# NRF24L01.net
KiCad netlist of a schematic drawn in Altium Designer
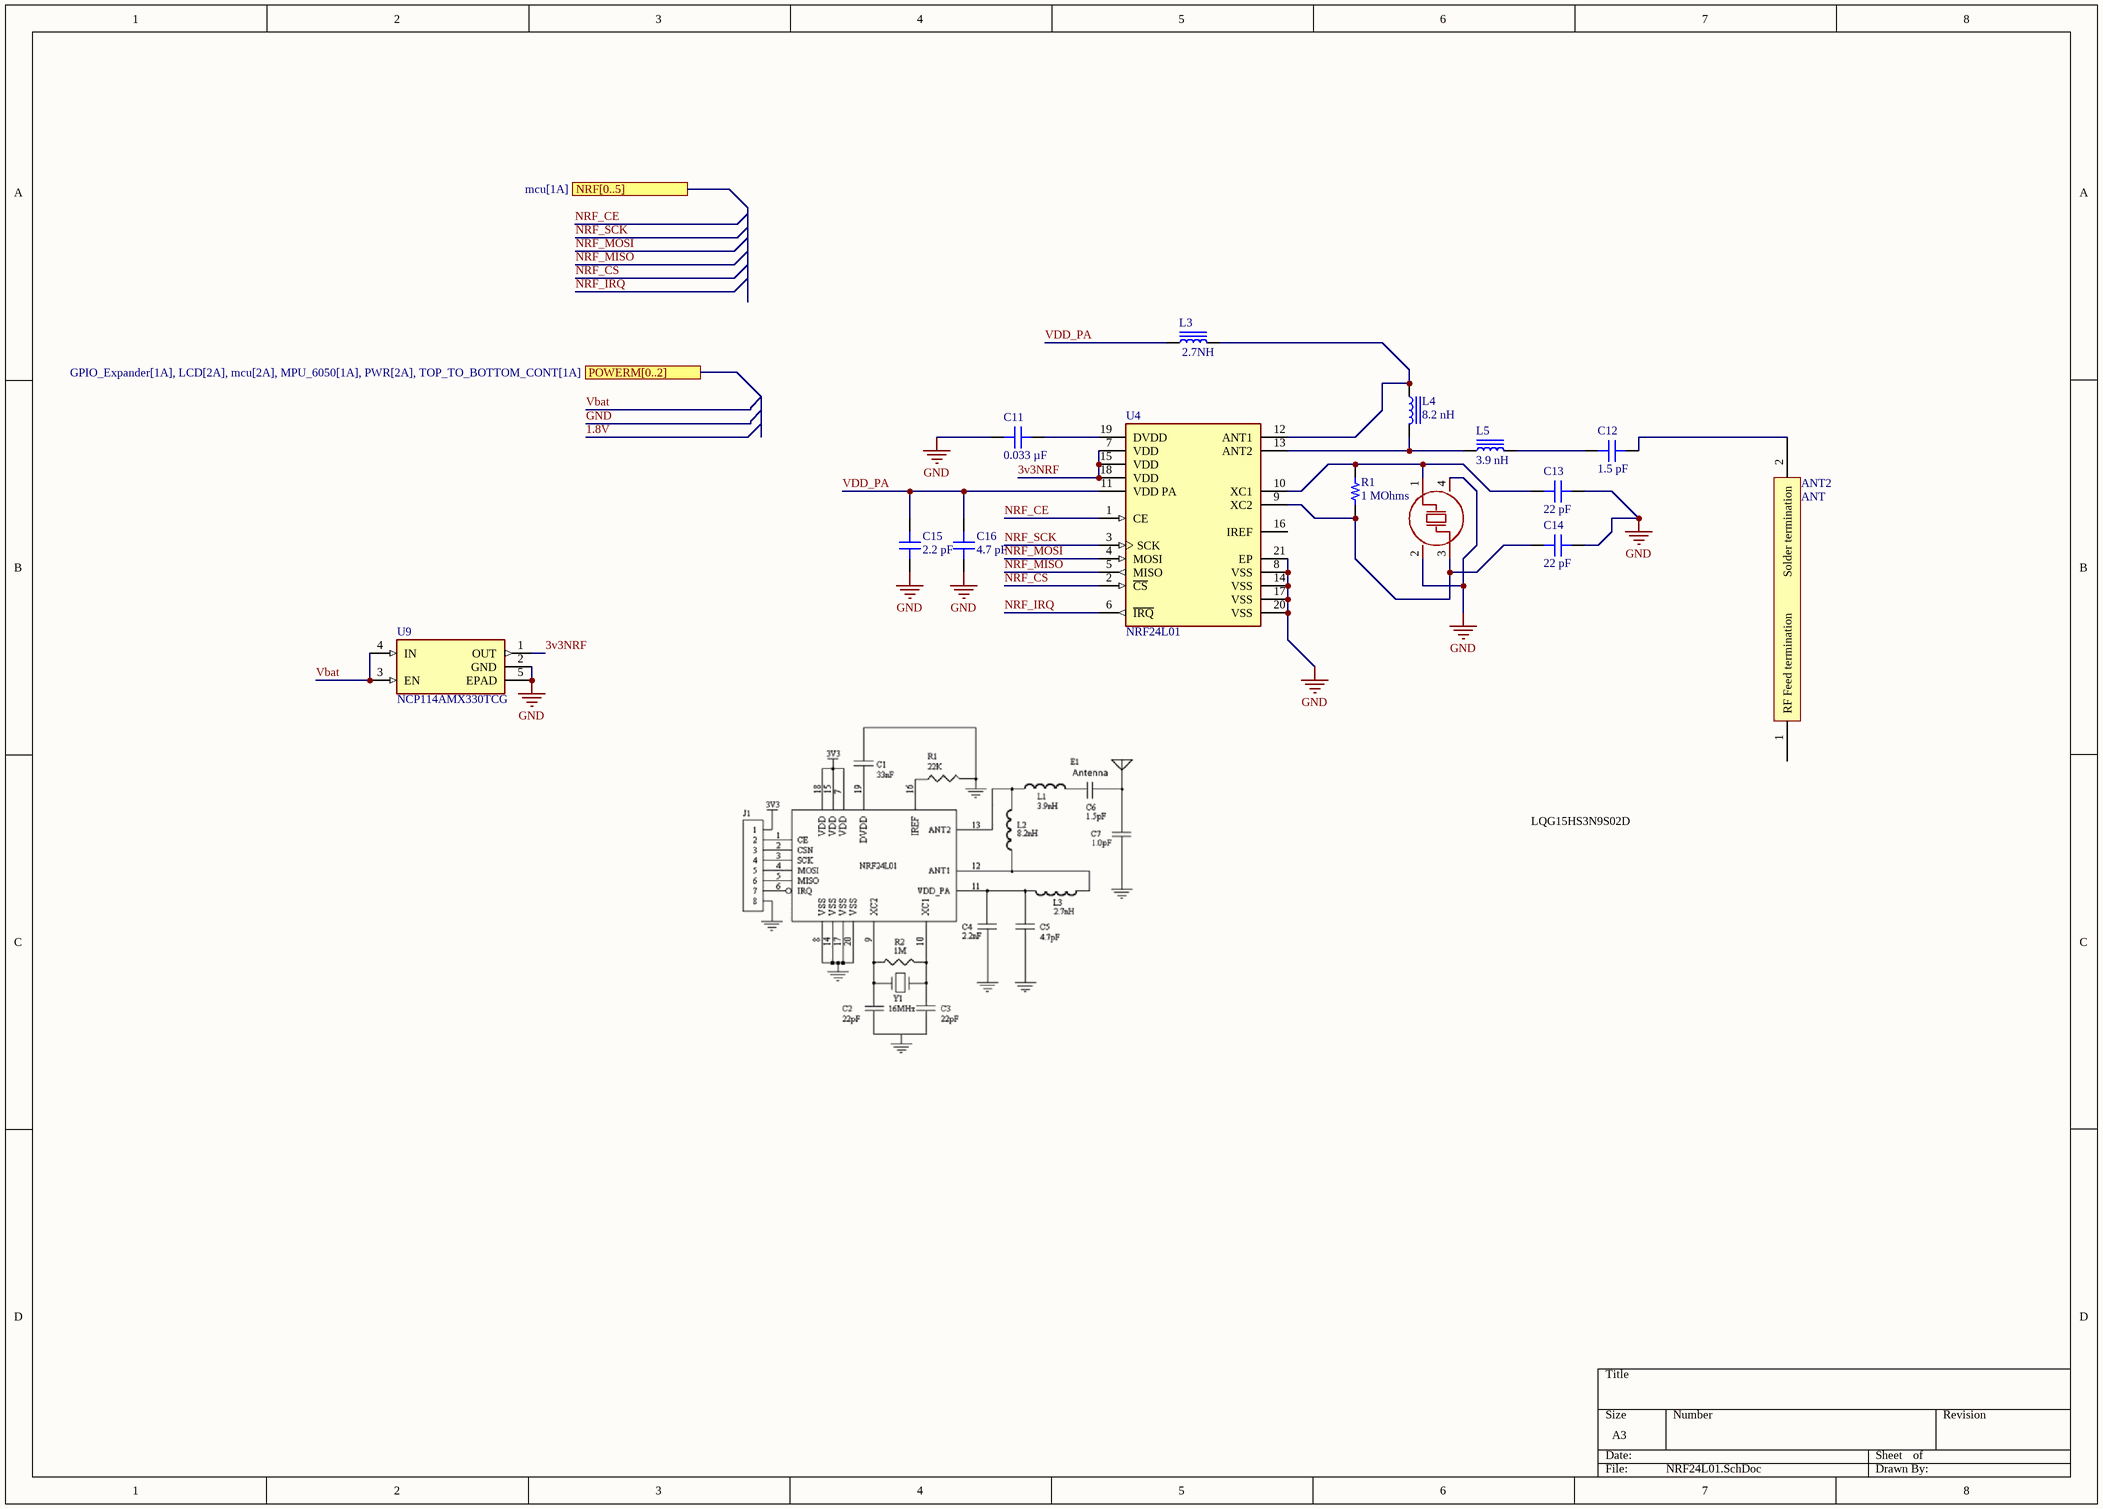
[diagram p0: NRF24L01.SchDoc]

(export (version "E")
  (design (tool "Eeschema 10.0.6"))
  (components
    (comp (ref "ANT2")
      (value "ANT")
      (footprint "CAPC3216X13N")
      (fields
        (field (name "MFR.PART #") "2450AT18D0100E")
        (field (name "JLCPCB PART #") "C2917718")
        (field (name "MANUFACTURER") "Johanson Dielectrics")
      )
      (libsource (lib "ANT") (part "ANT"))
    )
    (comp (ref "C11")
      (value "~")
      (footprint "CAP 0402_1005")
      (description "CAP CER 0.033UF 10V X7R 0402")
      (fields
        (field (name "CAPACITANCE") "0.033 µF")
        (field (name "MFR.PART #") "0402B333K160NT")
        (field (name "JLCPCB PART #") "C60425")
      )
      (libsource (lib "Celestial Altium Library - altium_library") (part "Capacitor"))
    )
    (comp (ref "C12")
      (value "~")
      (footprint "CAP 0402_1005")
      (description "CAP CER 1.5PF 250V C0G/NP0 0402")
      (fields
        (field (name "CAPACITANCE") "1.5 pF")
        (field (name "MFR.PART #") "0402CG1R5C500NT")
        (field (name "JLCPCB PART #") "C1552")
      )
      (libsource (lib "Celestial Altium Library - altium_library") (part "Capacitor"))
    )
    (comp (ref "C13")
      (value "~")
      (footprint "CAP 0402_1005")
      (description "CAP CER 22PF 200V C0G/NP0 0402")
      (fields
        (field (name "CAPACITANCE") "22 pF")
        (field (name "MFR.PART #") "0402CG220J500NT")
        (field (name "JLCPCB PART #") "C1555")
      )
      (libsource (lib "Celestial Altium Library - altium_library") (part "Capacitor"))
    )
    (comp (ref "C14")
      (value "~")
      (footprint "CAP 0402_1005")
      (description "CAP CER 22PF 200V C0G/NP0 0402")
      (fields
        (field (name "CAPACITANCE") "22 pF")
        (field (name "MFR.PART #") "0402CG220J500NT")
        (field (name "JLCPCB PART #") "C1555")
      )
      (libsource (lib "Celestial Altium Library - altium_library") (part "Capacitor"))
    )
    (comp (ref "C15")
      (value "~")
      (footprint "CAP 0402_1005")
      (description "CAP CER 2.2PF 250V C0G/NP0 0402")
      (fields
        (field (name "CAPACITANCE") "2.2 pF")
        (field (name "MFR.PART #") "C1559")
        (field (name "JLCPCB PART #") "0402CG2R2C500NT")
      )
      (libsource (lib "Celestial Altium Library - altium_library") (part "Capacitor"))
    )
    (comp (ref "C16")
      (value "~")
      (footprint "CAP 0402_1005")
      (description "CAP CER 4.7PF 200V C0G/NP0 0402")
      (fields
        (field (name "CAPACITANCE") "4.7 pF")
        (field (name "MFR.PART #") "0402CG4R7C500NT")
        (field (name "JLCPCB PART #") "C1569")
      )
      (libsource (lib "Celestial Altium Library - altium_library") (part "Capacitor"))
    )
    (comp (ref "L3")
      (value "2.7NH")
      (footprint "IND 0402_1005 RF WW")
      (description "FIXED IND 2.7NH 640MA 120MOHM SM")
      (fields (field (name "MFR.PART #") "CS0402-2N7B-S") (field (name "JLCPCB PART #") "C142182"))
      (libsource (lib "Celestial Altium Library - altium_library") (part "Inductor"))
    )
    (comp (ref "L4")
      (value "8.2 nH")
      (footprint "Murata LQW15 0402")
      (description "FIXED IND 8.2NH 1.5A 0.069OHM SM")
      (fields (field (name "MFR.PART #") "LQW15AN8N2G80D") (field (name "JLCPCB PART #") "C307610"))
      (libsource (lib "Celestial Altium Library - altium_library") (part "Inductor"))
    )
    (comp (ref "L5")
      (value "3.9 nH")
      (footprint "Murata LQW15 0402")
      (description "FIXED IND 3.9NH 900MA 0.04OHM SM")
      (fields (field (name "MFR.PART #") "LQG15HS3N9S02D") (field (name "JLCPCB PART #") "C77109"))
      (libsource (lib "Celestial Altium Library - altium_library") (part "Inductor"))
    )
    (comp (ref "R1")
      (value "1 MOhms")
      (footprint "RES 0402_1005")
      (description "RES SMD 1M OHM 1% 1/10W 0402")
      (fields
        (field (name "MANUFACTURER") "UNI-ROYAL(Uniroyal Elec)")
        (field (name "MFR.PART #") "0402WGF1004TCE")
      )
      (libsource (lib "Celestial Altium Library - altium_library") (part "Resistor"))
    )
    (comp (ref "U4")
      (value "NRF24L01")
      (footprint "FP-NRF24L01-IPC_C")
      (description "IC RF TXRX ISM>1GHZ 20VFQFN")
      (fields (field (name "MFR.PART #") "NRF24L01P-R") (field (name "JLCPCB PART #") "C8791"))
      (libsource (lib "Altium Content Vault") (part "c1991f80fab2a73cc9c289ab500ff3d"))
    )
    (comp (ref "U9")
      (value "NCP114AMX330TCG")
      (footprint "REG_NCP114AMX330TCG")
      (description "Linear Voltage Regulator IC Positive Fixed 1 Output 300mA 4-UDFN (1.0x1.0)")
      (fields (field (name "MANUFACTURER") "onsemi") (field (name "JLCPCB PART #") "C133056"))
      (libsource (lib "NCP114AMX330TCG") (part "NCP114AMX330TCG"))
    )
    (comp (ref "X2")
      (value "16MHz")
      (footprint "CRYSTAL-SMD_4P-L3.2-W2.5-BL")
      (fields
        (field (name "MFR.PART #") "ABM8G-16.000MHZ-18-D2Y-T")
        (field (name "JLCPCB PART #") "C1985423")
        (field (name "MANUFACTURER") "Abracon LLC")
      )
      (libsource (lib "altium-import") (part "root_3_ABM8G-16.000MHZ-18-D2Y-T_"))
    )
  )
  (nets
    (net (code "11") (name "/3v3NRF") (class "Default")
      (node (ref "U4") (pin "15") (pinfunction "VDD_15") (pintype "power_in"))
      (node (ref "U4") (pin "18") (pinfunction "VDD_18") (pintype "power_in"))
      (node (ref "U4") (pin "7") (pinfunction "VDD_7") (pintype "power_in"))
      (node (ref "U9") (pin "1") (pinfunction "OUT_1") (pintype "output"))
    )
    (net (code "13") (name "/NRF_CE") (class "Default")
      (node (ref "U4") (pin "1") (pinfunction "CE_1") (pintype "input"))
    )
    (net (code "14") (name "/NRF_CS") (class "Default")
      (node (ref "U4") (pin "2") (pinfunction "~{CS}_2") (pintype "input"))
    )
    (net (code "15") (name "/NRF_IRQ") (class "Default")
      (node (ref "U4") (pin "6") (pinfunction "~{IRQ}_6") (pintype "output"))
    )
    (net (code "16") (name "/NRF_MISO") (class "Default")
      (node (ref "U4") (pin "5") (pinfunction "MISO_5") (pintype "output"))
    )
    (net (code "17") (name "/NRF_MOSI") (class "Default")
      (node (ref "U4") (pin "4") (pinfunction "MOSI_4") (pintype "input"))
    )
    (net (code "18") (name "/NRF_SCK") (class "Default")
      (node (ref "U4") (pin "3") (pinfunction "SCK_3") (pintype "input"))
    )
    (net (code "20") (name "/VDD_PA") (class "Default")
      (node (ref "C15") (pin "2") (pinfunction "2_2") (pintype "passive"))
      (node (ref "C16") (pin "2") (pinfunction "2_2") (pintype "passive"))
      (node (ref "L3") (pin "1") (pinfunction "1_1") (pintype "passive"))
      (node (ref "U4") (pin "11") (pinfunction "VDD_PA_11") (pintype "power_in"))
    )
    (net (code "21") (name "/Vbat") (class "Default")
      (node (ref "U9") (pin "3") (pinfunction "EN_3") (pintype "input"))
      (node (ref "U9") (pin "4") (pinfunction "IN_4") (pintype "input"))
    )
    (net (code "22") (name "GND") (class "Default")
      (node (ref "C11") (pin "1") (pinfunction "1_1") (pintype "passive"))
      (node (ref "C13") (pin "2") (pinfunction "2_2") (pintype "passive"))
      (node (ref "C14") (pin "2") (pinfunction "2_2") (pintype "passive"))
      (node (ref "C15") (pin "1") (pinfunction "1_1") (pintype "passive"))
      (node (ref "C16") (pin "1") (pinfunction "1_1") (pintype "passive"))
      (node (ref "U4") (pin "14") (pinfunction "VSS_14") (pintype "power_in"))
      (node (ref "U4") (pin "17") (pinfunction "VSS_17") (pintype "power_in"))
      (node (ref "U4") (pin "20") (pinfunction "VSS_20") (pintype "power_in"))
      (node (ref "U4") (pin "21") (pinfunction "EP_21") (pintype "power_in"))
      (node (ref "U4") (pin "8") (pinfunction "VSS_8") (pintype "power_in"))
      (node (ref "U9") (pin "2") (pinfunction "GND_2") (pintype "power_in"))
      (node (ref "U9") (pin "5") (pinfunction "EPAD_5") (pintype "passive"))
      (node (ref "X2") (pin "2") (pinfunction "2_2") (pintype "passive"))
      (node (ref "X2") (pin "4") (pinfunction "4_4") (pintype "passive"))
    )
    (net (code "23") (name "Net-(ANT2-Solder_termination)") (class "Default")
      (node (ref "ANT2") (pin "2") (pinfunction "Solder_termination_2") (pintype "passive"))
      (node (ref "C12") (pin "2") (pinfunction "2_2") (pintype "passive"))
    )
    (net (code "24") (name "Net-(C12-Pad1)") (class "Default")
      (node (ref "C12") (pin "1") (pinfunction "1_1") (pintype "passive"))
      (node (ref "L5") (pin "2") (pinfunction "2_2") (pintype "passive"))
    )
    (net (code "25") (name "Net-(U4-ANT1)") (class "Default")
      (node (ref "L3") (pin "2") (pinfunction "2_2") (pintype "passive"))
      (node (ref "L4") (pin "1") (pinfunction "1_1") (pintype "passive"))
      (node (ref "U4") (pin "12") (pinfunction "ANT1_12") (pintype "passive"))
    )
    (net (code "26") (name "Net-(U4-ANT2)") (class "Default")
      (node (ref "L4") (pin "2") (pinfunction "2_2") (pintype "passive"))
      (node (ref "L5") (pin "1") (pinfunction "1_1") (pintype "passive"))
      (node (ref "U4") (pin "13") (pinfunction "ANT2_13") (pintype "passive"))
    )
    (net (code "27") (name "Net-(U4-DVDD)") (class "Default")
      (node (ref "C11") (pin "2") (pinfunction "2_2") (pintype "passive"))
      (node (ref "U4") (pin "19") (pinfunction "DVDD_19") (pintype "power_in"))
    )
    (net (code "28") (name "Net-(U4-XC1)") (class "Default")
      (node (ref "C13") (pin "1") (pinfunction "1_1") (pintype "passive"))
      (node (ref "R1") (pin "2") (pinfunction "2_2") (pintype "passive"))
      (node (ref "U4") (pin "10") (pinfunction "XC1_10") (pintype "passive"))
      (node (ref "X2") (pin "1") (pinfunction "OSC1_1") (pintype "passive"))
    )
    (net (code "29") (name "Net-(U4-XC2)") (class "Default")
      (node (ref "C14") (pin "1") (pinfunction "1_1") (pintype "passive"))
      (node (ref "R1") (pin "1") (pinfunction "1_1") (pintype "passive"))
      (node (ref "U4") (pin "9") (pinfunction "XC2_9") (pintype "passive"))
      (node (ref "X2") (pin "3") (pinfunction "OSC2_3") (pintype "passive"))
    )
    (net (code "30") (name "unconnected-(ANT2-RF_Feed_termination-Pad1)") (class "Default")
      (node (ref "ANT2") (pin "1") (pinfunction "RF_Feed_termination_1") (pintype "passive"))
    )
    (net (code "31") (name "unconnected-(U4-IREF-Pad16)") (class "Default")
      (node (ref "U4") (pin "16") (pinfunction "IREF_16") (pintype "passive"))
    )
  )
)
